# 05-VIDEO_TEST_PATTERN.net
KiCad netlist of a schematic drawn in Altium Designer
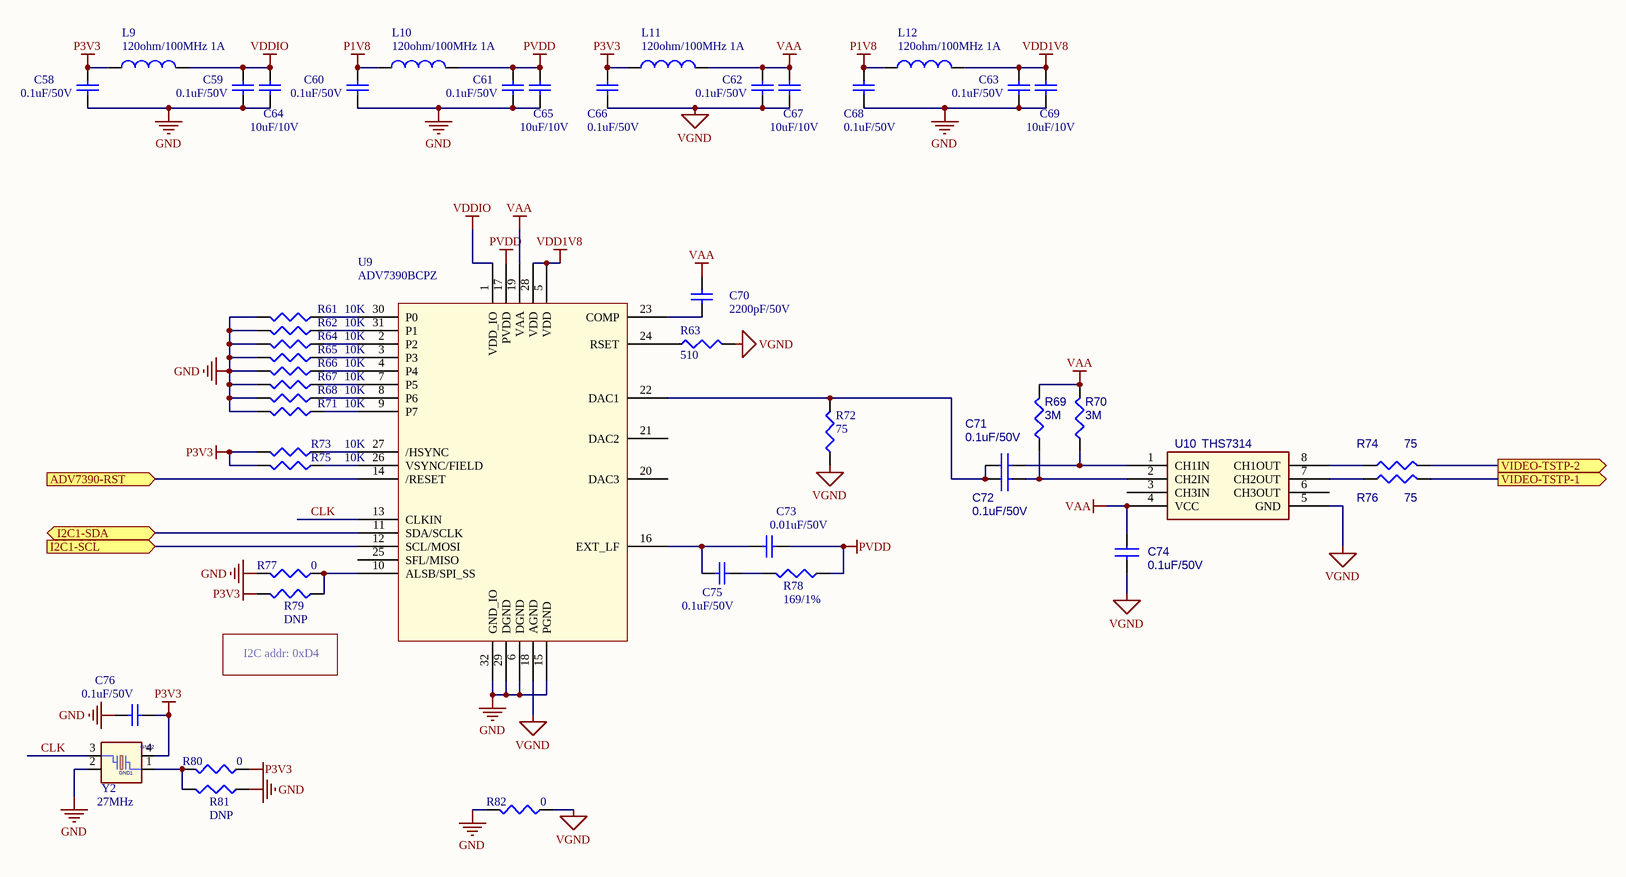
[diagram p0: 05-VIDEO_TEST_PATTERN.SchDoc]

(export (version "E")
  (design (tool "Eeschema 10.0.6"))
  (components
    (comp (ref "C58")
      (value "0.1uF/50V")
      (footprint "0402")
      (description "Capacitor")
      (fields (field (name "PUBLISHER") "Altium Limited"))
      (libsource (lib "Miscellaneous Devices") (part "Cap"))
    )
    (comp (ref "C59")
      (value "0.1uF/50V")
      (footprint "0402")
      (description "Capacitor")
      (fields (field (name "PUBLISHER") "Altium Limited"))
      (libsource (lib "Miscellaneous Devices") (part "Cap"))
    )
    (comp (ref "C60")
      (value "0.1uF/50V")
      (footprint "0402")
      (description "Capacitor")
      (fields (field (name "PUBLISHER") "Altium Limited"))
      (libsource (lib "Miscellaneous Devices") (part "Cap"))
    )
    (comp (ref "C61")
      (value "0.1uF/50V")
      (footprint "0402")
      (description "Capacitor")
      (fields (field (name "PUBLISHER") "Altium Limited"))
      (libsource (lib "Miscellaneous Devices") (part "Cap"))
    )
    (comp (ref "C62")
      (value "0.1uF/50V")
      (footprint "0402")
      (description "Capacitor")
      (fields (field (name "PUBLISHER") "Altium Limited"))
      (libsource (lib "Miscellaneous Devices") (part "Cap"))
    )
    (comp (ref "C63")
      (value "0.1uF/50V")
      (footprint "0402")
      (description "Capacitor")
      (fields (field (name "PUBLISHER") "Altium Limited"))
      (libsource (lib "Miscellaneous Devices") (part "Cap"))
    )
    (comp (ref "C64")
      (value "10uF/10V")
      (footprint "0805")
      (description "Capacitor")
      (fields (field (name "PUBLISHER") "Altium Limited"))
      (libsource (lib "Miscellaneous Devices") (part "Cap"))
    )
    (comp (ref "C65")
      (value "10uF/10V")
      (footprint "0805")
      (description "Capacitor")
      (fields (field (name "PUBLISHER") "Altium Limited"))
      (libsource (lib "Miscellaneous Devices") (part "Cap"))
    )
    (comp (ref "C66")
      (value "0.1uF/50V")
      (footprint "0402")
      (description "Capacitor")
      (fields (field (name "PUBLISHER") "Altium Limited"))
      (libsource (lib "Miscellaneous Devices") (part "Cap"))
    )
    (comp (ref "C67")
      (value "10uF/10V")
      (footprint "0805")
      (description "Capacitor")
      (fields (field (name "PUBLISHER") "Altium Limited"))
      (libsource (lib "Miscellaneous Devices") (part "Cap"))
    )
    (comp (ref "C68")
      (value "0.1uF/50V")
      (footprint "0402")
      (description "Capacitor")
      (fields (field (name "PUBLISHER") "Altium Limited"))
      (libsource (lib "Miscellaneous Devices") (part "Cap"))
    )
    (comp (ref "C69")
      (value "10uF/10V")
      (footprint "0805")
      (description "Capacitor")
      (fields (field (name "PUBLISHER") "Altium Limited"))
      (libsource (lib "Miscellaneous Devices") (part "Cap"))
    )
    (comp (ref "C70")
      (value "2200pF/50V")
      (footprint "0402")
      (description "Capacitor")
      (fields (field (name "PUBLISHER") "Altium Limited"))
      (libsource (lib "Miscellaneous Devices") (part "Cap"))
    )
    (comp (ref "C71") (value "0.1uF/50V") (libsource (lib "*") (part "CAP")))
    (comp (ref "C72") (value "0.1uF/50V") (libsource (lib "*") (part "CAP")))
    (comp (ref "C73")
      (value "0.01uF/50V")
      (footprint "0402")
      (description "Capacitor")
      (fields (field (name "PUBLISHER") "Altium Limited"))
      (libsource (lib "Miscellaneous Devices") (part "Cap"))
    )
    (comp (ref "C74") (value "0.1uF/50V") (libsource (lib "*") (part "CAP")))
    (comp (ref "C75")
      (value "0.1uF/50V")
      (footprint "0402")
      (description "Capacitor")
      (fields (field (name "PUBLISHER") "Altium Limited"))
      (libsource (lib "Miscellaneous Devices") (part "Cap"))
    )
    (comp (ref "C76")
      (value "0.1uF/50V")
      (footprint "0402")
      (description "Capacitor")
      (fields (field (name "PUBLISHER") "Altium Limited"))
      (libsource (lib "Miscellaneous Devices") (part "Cap"))
    )
    (comp (ref "L9")
      (value "120ohm/100MHz 1A")
      (footprint "0603")
      (description "Inductor")
      (fields (field (name "PUBLISHER") "Altium Limited"))
      (libsource (lib "Miscellaneous Devices") (part "Inductor"))
    )
    (comp (ref "L10")
      (value "120ohm/100MHz 1A")
      (footprint "0603")
      (description "Inductor")
      (fields (field (name "PUBLISHER") "Altium Limited"))
      (libsource (lib "Miscellaneous Devices") (part "Inductor"))
    )
    (comp (ref "L11")
      (value "120ohm/100MHz 1A")
      (footprint "0603")
      (description "Inductor")
      (fields (field (name "PUBLISHER") "Altium Limited"))
      (libsource (lib "Miscellaneous Devices") (part "Inductor"))
    )
    (comp (ref "L12")
      (value "120ohm/100MHz 1A")
      (footprint "0603")
      (description "Inductor")
      (fields (field (name "PUBLISHER") "Altium Limited"))
      (libsource (lib "Miscellaneous Devices") (part "Inductor"))
    )
    (comp (ref "R61") (value "10K") (footprint "0402") (libsource (lib "*") (part "CR16-1003FM")))
    (comp (ref "R62") (value "10K") (footprint "0402") (libsource (lib "*") (part "CR16-1003FM")))
    (comp (ref "R63") (value "510") (footprint "0402") (libsource (lib "*") (part "CR16-1003FM")))
    (comp (ref "R64") (value "10K") (footprint "0402") (libsource (lib "*") (part "CR16-1003FM")))
    (comp (ref "R65") (value "10K") (footprint "0402") (libsource (lib "*") (part "CR16-1003FM")))
    (comp (ref "R66") (value "10K") (footprint "0402") (libsource (lib "*") (part "CR16-1003FM")))
    (comp (ref "R67") (value "10K") (footprint "0402") (libsource (lib "*") (part "CR16-1003FM")))
    (comp (ref "R68") (value "10K") (footprint "0402") (libsource (lib "*") (part "CR16-1003FM")))
    (comp (ref "R69")
      (value "3M")
      (fields (field (name "PART NUMBER") "SD02810028L"))
      (libsource (lib "*") (part "R"))
    )
    (comp (ref "R70")
      (value "3M")
      (fields (field (name "PART NUMBER") "SD02810028L"))
      (libsource (lib "*") (part "R"))
    )
    (comp (ref "R71") (value "10K") (footprint "0402") (libsource (lib "*") (part "CR16-1003FM")))
    (comp (ref "R72") (value "75") (footprint "0402") (libsource (lib "*") (part "CR16-1003FM")))
    (comp (ref "R73") (value "10K") (footprint "0402") (libsource (lib "*") (part "CR16-1003FM")))
    (comp (ref "R74")
      (value "75")
      (fields (field (name "PART NUMBER") "SD02810028L"))
      (libsource (lib "*") (part "R"))
    )
    (comp (ref "R75") (value "10K") (footprint "0402") (libsource (lib "*") (part "CR16-1003FM")))
    (comp (ref "R76")
      (value "75")
      (fields (field (name "PART NUMBER") "SD02810028L"))
      (libsource (lib "*") (part "R"))
    )
    (comp (ref "R77") (value "0") (footprint "0402") (libsource (lib "*") (part "CR16-1003FM")))
    (comp (ref "R78") (value "169/1%") (footprint "0402") (libsource (lib "*") (part "CR16-1003FM")))
    (comp (ref "R79") (value "DNP") (footprint "0402") (libsource (lib "*") (part "CR16-1003FM")))
    (comp (ref "R80") (value "0") (footprint "0402") (libsource (lib "*") (part "CR16-1003FM")))
    (comp (ref "R81") (value "DNP") (footprint "0402") (libsource (lib "*") (part "CR16-1003FM")))
    (comp (ref "R82") (value "0") (footprint "0402") (libsource (lib "*") (part "CR16-1003FM")))
    (comp (ref "U9")
      (value "ADV7390BCPZ")
      (footprint "LFCSP32")
      (libsource (lib "Schlib") (part "ADV7390BCPZ"))
    )
    (comp (ref "U10") (value "THS7314") (libsource (lib "*") (part "THS7314")))
    (comp (ref "Y2")
      (value "27MHz")
      (footprint "XTAL4_SX_3225")
      (description "XTAL 28.63636MHZ 10PF RSN -- SMT")
      (libsource (lib "*") (part "CRYSTAL_JXS63"))
    )
  )
  (nets
    (net (code "1") (name "/ADV7390-RST") (class "Default")
      (node (ref "U9") (pin "14") (pinfunction "/RESET_14") (pintype "passive"))
    )
    (net (code "2") (name "/CLK") (class "Default")
      (node (ref "U9") (pin "13") (pinfunction "CLKIN_13") (pintype "passive"))
      (node (ref "Y2") (pin "3") (pinfunction "3_3") (pintype "passive"))
    )
    (net (code "3") (name "/I2C1-SCL") (class "Default")
      (node (ref "U9") (pin "12") (pinfunction "SCL/MOSI_12") (pintype "passive"))
    )
    (net (code "4") (name "/I2C1-SDA") (class "Default")
      (node (ref "U9") (pin "11") (pinfunction "SDA/SCLK_11") (pintype "passive"))
    )
    (net (code "5") (name "/VIDEO-TSTP-1") (class "Default")
      (node (ref "R76") (pin "2") (pinfunction "2_2") (pintype "passive"))
    )
    (net (code "6") (name "/VIDEO-TSTP-2") (class "Default")
      (node (ref "R74") (pin "2") (pinfunction "2_2") (pintype "passive"))
    )
    (net (code "7") (name "GND") (class "Default")
      (node (ref "C58") (pin "2") (pinfunction "2_2") (pintype "passive"))
      (node (ref "C59") (pin "2") (pinfunction "2_2") (pintype "passive"))
      (node (ref "C60") (pin "2") (pinfunction "2_2") (pintype "passive"))
      (node (ref "C61") (pin "2") (pinfunction "2_2") (pintype "passive"))
      (node (ref "C63") (pin "2") (pinfunction "2_2") (pintype "passive"))
      (node (ref "C64") (pin "2") (pinfunction "2_2") (pintype "passive"))
      (node (ref "C65") (pin "2") (pinfunction "2_2") (pintype "passive"))
      (node (ref "C68") (pin "2") (pinfunction "2_2") (pintype "passive"))
      (node (ref "C69") (pin "2") (pinfunction "2_2") (pintype "passive"))
      (node (ref "C76") (pin "2") (pinfunction "2_2") (pintype "passive"))
      (node (ref "R61") (pin "2") (pinfunction "2_2") (pintype "passive"))
      (node (ref "R62") (pin "2") (pinfunction "2_2") (pintype "passive"))
      (node (ref "R64") (pin "2") (pinfunction "2_2") (pintype "passive"))
      (node (ref "R65") (pin "2") (pinfunction "2_2") (pintype "passive"))
      (node (ref "R66") (pin "2") (pinfunction "2_2") (pintype "passive"))
      (node (ref "R67") (pin "2") (pinfunction "2_2") (pintype "passive"))
      (node (ref "R68") (pin "2") (pinfunction "2_2") (pintype "passive"))
      (node (ref "R71") (pin "2") (pinfunction "2_2") (pintype "passive"))
      (node (ref "R77") (pin "2") (pinfunction "2_2") (pintype "passive"))
      (node (ref "R81") (pin "1") (pinfunction "1_1") (pintype "passive"))
      (node (ref "R82") (pin "2") (pinfunction "2_2") (pintype "passive"))
      (node (ref "U9") (pin "15") (pinfunction "PGND_15") (pintype "passive"))
      (node (ref "U9") (pin "29") (pinfunction "DGND_29") (pintype "passive"))
      (node (ref "U9") (pin "32") (pinfunction "GND_IO_32") (pintype "passive"))
      (node (ref "U9") (pin "6") (pinfunction "DGND_6") (pintype "passive"))
      (node (ref "Y2") (pin "2") (pinfunction "GND1_2") (pintype "power_in"))
    )
    (net (code "8") (name "Net-(C75-Pad2)") (class "Default")
      (node (ref "C75") (pin "2") (pinfunction "2_2") (pintype "passive"))
      (node (ref "R78") (pin "2") (pinfunction "2_2") (pintype "passive"))
    )
    (net (code "9") (name "Net-(R80-Pad2)") (class "Default")
      (node (ref "R80") (pin "2") (pinfunction "2_2") (pintype "passive"))
      (node (ref "R81") (pin "2") (pinfunction "2_2") (pintype "passive"))
      (node (ref "Y2") (pin "1") (pinfunction "1_1") (pintype "passive"))
    )
    (net (code "10") (name "Net-(U9-ALSB{slash}SPI_SS)") (class "Default")
      (node (ref "R77") (pin "1") (pinfunction "1_1") (pintype "passive"))
      (node (ref "R79") (pin "1") (pinfunction "1_1") (pintype "passive"))
      (node (ref "U9") (pin "10") (pinfunction "ALSB/SPI_SS_10") (pintype "passive"))
    )
    (net (code "11") (name "Net-(U9-COMP)") (class "Default")
      (node (ref "C70") (pin "2") (pinfunction "2_2") (pintype "passive"))
      (node (ref "U9") (pin "23") (pinfunction "COMP_23") (pintype "passive"))
    )
    (net (code "12") (name "Net-(U9-DAC1)") (class "Default")
      (node (ref "C71") (pin "1") (pinfunction "1_1") (pintype "passive"))
      (node (ref "C72") (pin "1") (pinfunction "1_1") (pintype "passive"))
      (node (ref "R72") (pin "2") (pinfunction "2_2") (pintype "passive"))
      (node (ref "U9") (pin "22") (pinfunction "DAC1_22") (pintype "passive"))
    )
    (net (code "13") (name "Net-(U9-EXT_LF)") (class "Default")
      (node (ref "C73") (pin "1") (pinfunction "1_1") (pintype "passive"))
      (node (ref "C75") (pin "1") (pinfunction "1_1") (pintype "passive"))
      (node (ref "U9") (pin "16") (pinfunction "EXT_LF_16") (pintype "passive"))
    )
    (net (code "14") (name "Net-(U9-P0)") (class "Default")
      (node (ref "R61") (pin "1") (pinfunction "1_1") (pintype "passive"))
      (node (ref "U9") (pin "30") (pinfunction "P0_30") (pintype "passive"))
    )
    (net (code "15") (name "Net-(U9-P1)") (class "Default")
      (node (ref "R62") (pin "1") (pinfunction "1_1") (pintype "passive"))
      (node (ref "U9") (pin "31") (pinfunction "P1_31") (pintype "passive"))
    )
    (net (code "16") (name "Net-(U9-P2)") (class "Default")
      (node (ref "R64") (pin "1") (pinfunction "1_1") (pintype "passive"))
      (node (ref "U9") (pin "2") (pinfunction "P2_2") (pintype "passive"))
    )
    (net (code "17") (name "Net-(U9-P3)") (class "Default")
      (node (ref "R65") (pin "1") (pinfunction "1_1") (pintype "passive"))
      (node (ref "U9") (pin "3") (pinfunction "P3_3") (pintype "passive"))
    )
    (net (code "18") (name "Net-(U9-P4)") (class "Default")
      (node (ref "R66") (pin "1") (pinfunction "1_1") (pintype "passive"))
      (node (ref "U9") (pin "4") (pinfunction "P4_4") (pintype "passive"))
    )
    (net (code "19") (name "Net-(U9-P5)") (class "Default")
      (node (ref "R67") (pin "1") (pinfunction "1_1") (pintype "passive"))
      (node (ref "U9") (pin "7") (pinfunction "P5_7") (pintype "passive"))
    )
    (net (code "20") (name "Net-(U9-P6)") (class "Default")
      (node (ref "R68") (pin "1") (pinfunction "1_1") (pintype "passive"))
      (node (ref "U9") (pin "8") (pinfunction "P6_8") (pintype "passive"))
    )
    (net (code "21") (name "Net-(U9-P7)") (class "Default")
      (node (ref "R71") (pin "1") (pinfunction "1_1") (pintype "passive"))
      (node (ref "U9") (pin "9") (pinfunction "P7_9") (pintype "passive"))
    )
    (net (code "22") (name "Net-(U9-RSET)") (class "Default")
      (node (ref "R63") (pin "1") (pinfunction "1_1") (pintype "passive"))
      (node (ref "U9") (pin "24") (pinfunction "RSET_24") (pintype "passive"))
    )
    (net (code "23") (name "Net-(U9-VSYNC{slash}FIELD)") (class "Default")
      (node (ref "R75") (pin "1") (pinfunction "1_1") (pintype "passive"))
      (node (ref "U9") (pin "26") (pinfunction "VSYNC/FIELD_26") (pintype "passive"))
    )
    (net (code "24") (name "Net-(U9-{slash}HSYNC)") (class "Default")
      (node (ref "R73") (pin "1") (pinfunction "1_1") (pintype "passive"))
      (node (ref "U9") (pin "27") (pinfunction "/HSYNC_27") (pintype "passive"))
    )
    (net (code "25") (name "Net-(U10-CH1IN)") (class "Default")
      (node (ref "C71") (pin "2") (pinfunction "2_2") (pintype "passive"))
      (node (ref "R70") (pin "1") (pinfunction "1_1") (pintype "passive"))
      (node (ref "U10") (pin "1") (pinfunction "CH1IN_1") (pintype "passive"))
    )
    (net (code "26") (name "Net-(U10-CH1OUT)") (class "Default")
      (node (ref "R74") (pin "1") (pinfunction "1_1") (pintype "passive"))
      (node (ref "U10") (pin "8") (pinfunction "CH1OUT_8") (pintype "passive"))
    )
    (net (code "27") (name "Net-(U10-CH2IN)") (class "Default")
      (node (ref "C72") (pin "2") (pinfunction "2_2") (pintype "passive"))
      (node (ref "R69") (pin "1") (pinfunction "1_1") (pintype "passive"))
      (node (ref "U10") (pin "2") (pinfunction "CH2IN_2") (pintype "passive"))
    )
    (net (code "28") (name "Net-(U10-CH2OUT)") (class "Default")
      (node (ref "R76") (pin "1") (pinfunction "1_1") (pintype "passive"))
      (node (ref "U10") (pin "7") (pinfunction "CH2OUT_7") (pintype "passive"))
    )
    (net (code "29") (name "P1V8") (class "Default")
      (node (ref "C60") (pin "1") (pinfunction "1_1") (pintype "passive"))
      (node (ref "C68") (pin "1") (pinfunction "1_1") (pintype "passive"))
      (node (ref "L10") (pin "1") (pinfunction "1_1") (pintype "passive"))
      (node (ref "L12") (pin "1") (pinfunction "1_1") (pintype "passive"))
    )
    (net (code "30") (name "P3V3") (class "Default")
      (node (ref "C58") (pin "1") (pinfunction "1_1") (pintype "passive"))
      (node (ref "C66") (pin "1") (pinfunction "1_1") (pintype "passive"))
      (node (ref "C76") (pin "1") (pinfunction "1_1") (pintype "passive"))
      (node (ref "L11") (pin "1") (pinfunction "1_1") (pintype "passive"))
      (node (ref "L9") (pin "1") (pinfunction "1_1") (pintype "passive"))
      (node (ref "R73") (pin "2") (pinfunction "2_2") (pintype "passive"))
      (node (ref "R75") (pin "2") (pinfunction "2_2") (pintype "passive"))
      (node (ref "R79") (pin "2") (pinfunction "2_2") (pintype "passive"))
      (node (ref "R80") (pin "1") (pinfunction "1_1") (pintype "passive"))
      (node (ref "Y2") (pin "4") (pinfunction "GND2_4") (pintype "power_in"))
    )
    (net (code "31") (name "PVDD") (class "Default")
      (node (ref "C61") (pin "1") (pinfunction "1_1") (pintype "passive"))
      (node (ref "C65") (pin "1") (pinfunction "1_1") (pintype "passive"))
      (node (ref "C73") (pin "2") (pinfunction "2_2") (pintype "passive"))
      (node (ref "L10") (pin "2") (pinfunction "2_2") (pintype "passive"))
      (node (ref "R78") (pin "1") (pinfunction "1_1") (pintype "passive"))
      (node (ref "U9") (pin "17") (pinfunction "PVDD_17") (pintype "passive"))
    )
    (net (code "32") (name "VAA") (class "Default")
      (node (ref "C62") (pin "1") (pinfunction "1_1") (pintype "passive"))
      (node (ref "C67") (pin "1") (pinfunction "1_1") (pintype "passive"))
      (node (ref "C70") (pin "1") (pinfunction "1_1") (pintype "passive"))
      (node (ref "C74") (pin "1") (pinfunction "1_1") (pintype "passive"))
      (node (ref "L11") (pin "2") (pinfunction "2_2") (pintype "passive"))
      (node (ref "R69") (pin "2") (pinfunction "2_2") (pintype "passive"))
      (node (ref "R70") (pin "2") (pinfunction "2_2") (pintype "passive"))
      (node (ref "U10") (pin "4") (pinfunction "VCC_4") (pintype "passive"))
      (node (ref "U9") (pin "19") (pinfunction "VAA_19") (pintype "passive"))
    )
    (net (code "33") (name "VDD1V8") (class "Default")
      (node (ref "C63") (pin "1") (pinfunction "1_1") (pintype "passive"))
      (node (ref "C69") (pin "1") (pinfunction "1_1") (pintype "passive"))
      (node (ref "L12") (pin "2") (pinfunction "2_2") (pintype "passive"))
      (node (ref "U9") (pin "28") (pinfunction "VDD_28") (pintype "passive"))
      (node (ref "U9") (pin "5") (pinfunction "VDD_5") (pintype "passive"))
    )
    (net (code "34") (name "VDDIO") (class "Default")
      (node (ref "C59") (pin "1") (pinfunction "1_1") (pintype "passive"))
      (node (ref "C64") (pin "1") (pinfunction "1_1") (pintype "passive"))
      (node (ref "L9") (pin "2") (pinfunction "2_2") (pintype "passive"))
      (node (ref "U9") (pin "1") (pinfunction "VDD_IO_1") (pintype "passive"))
    )
    (net (code "35") (name "VGND") (class "Default")
      (node (ref "C62") (pin "2") (pinfunction "2_2") (pintype "passive"))
      (node (ref "C66") (pin "2") (pinfunction "2_2") (pintype "passive"))
      (node (ref "C67") (pin "2") (pinfunction "2_2") (pintype "passive"))
      (node (ref "C74") (pin "2") (pinfunction "2_2") (pintype "passive"))
      (node (ref "R63") (pin "2") (pinfunction "2_2") (pintype "passive"))
      (node (ref "R72") (pin "1") (pinfunction "1_1") (pintype "passive"))
      (node (ref "R82") (pin "1") (pinfunction "1_1") (pintype "passive"))
      (node (ref "U10") (pin "5") (pinfunction "GND_5") (pintype "passive"))
      (node (ref "U9") (pin "18") (pinfunction "AGND_18") (pintype "passive"))
    )
    (net (code "36") (name "unconnected-(U9-DAC2-Pad21)") (class "Default")
      (node (ref "U9") (pin "21") (pinfunction "DAC2_21") (pintype "passive"))
    )
    (net (code "37") (name "unconnected-(U9-DAC3-Pad20)") (class "Default")
      (node (ref "U9") (pin "20") (pinfunction "DAC3_20") (pintype "passive"))
    )
    (net (code "38") (name "unconnected-(U9-SFL{slash}MISO-Pad25)") (class "Default")
      (node (ref "U9") (pin "25") (pinfunction "SFL/MISO_25") (pintype "passive"))
    )
    (net (code "39") (name "unconnected-(U10-CH3IN-Pad3)") (class "Default")
      (node (ref "U10") (pin "3") (pinfunction "CH3IN_3") (pintype "passive"))
    )
    (net (code "40") (name "unconnected-(U10-CH3OUT-Pad6)") (class "Default")
      (node (ref "U10") (pin "6") (pinfunction "CH3OUT_6") (pintype "passive"))
    )
  )
)
